# EDU_High-Speed-Design_Power_2V5_1V5.net
KiCad netlist of a schematic drawn in Altium Designer
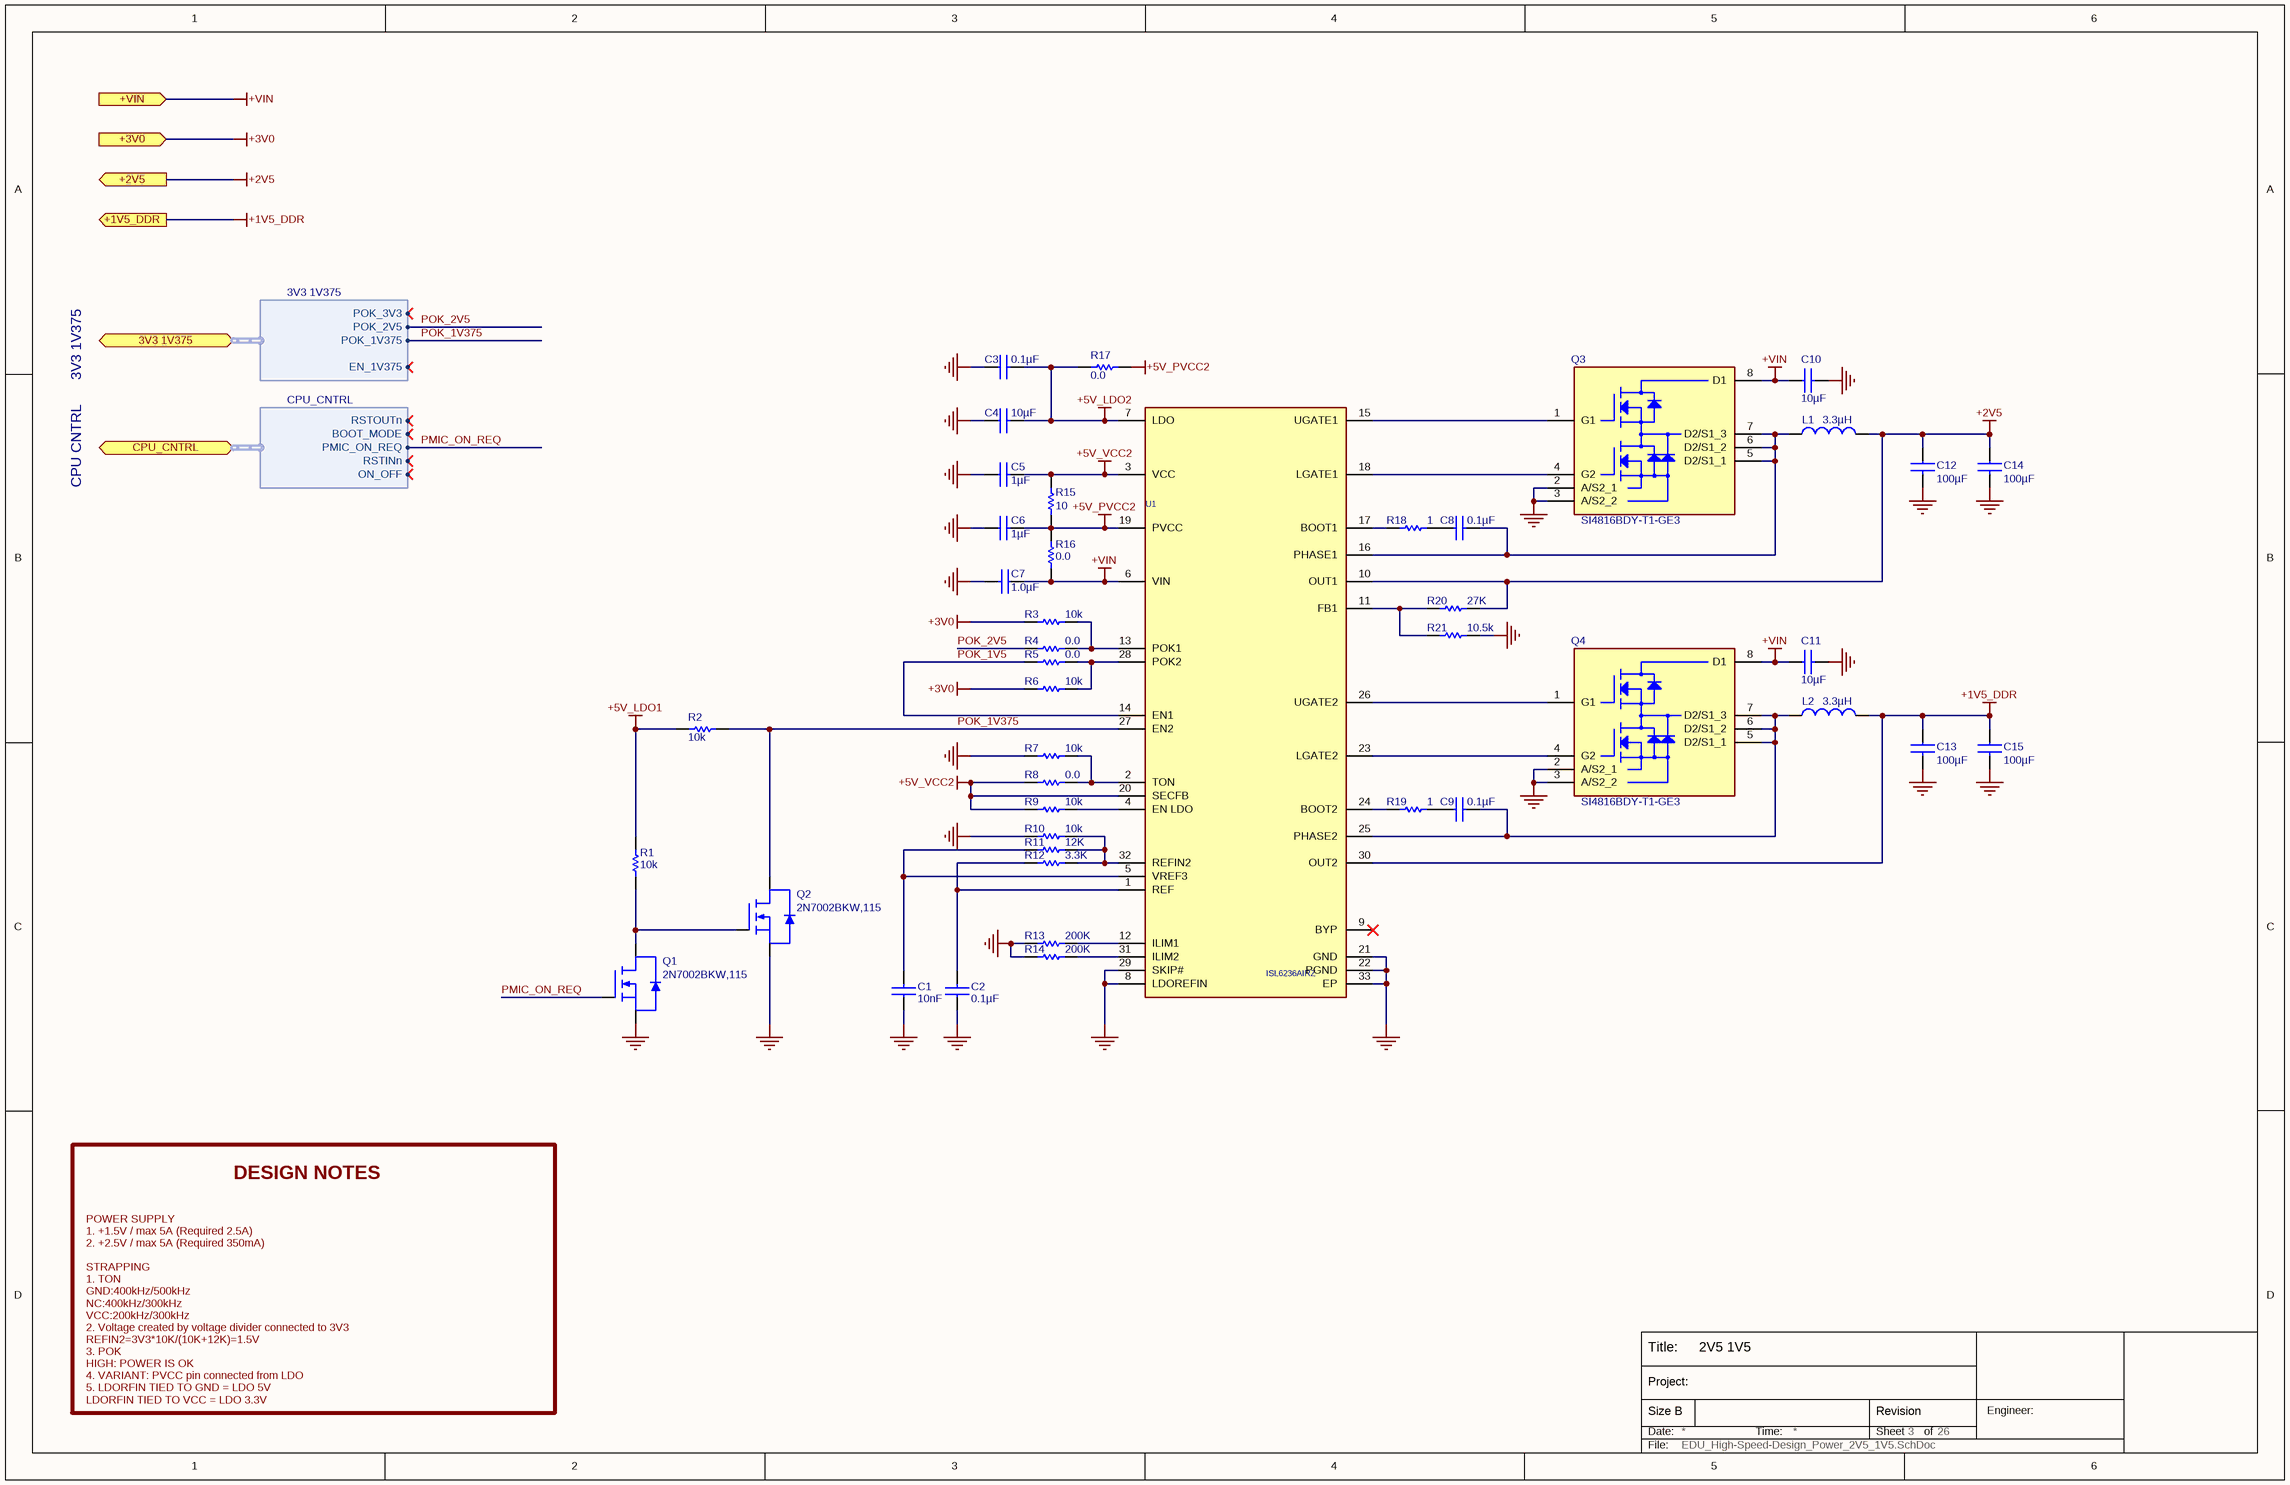
[diagram p0: EDU_High-Speed-Design_Power_2V5_1V5.SchDoc]

(export (version "E")
  (design (tool "Eeschema 10.0.6"))
  (components
    (comp (ref "C1")
      (value "10nF")
      (footprint "C0402")
      (description "CAP CER 10000PF 16V X7R 10% 0402")
      (fields
        (field (name "MANUFACTURER") "TDK Corporation")
        (field (name "MANUFACTURER PART NUMBER") "C1005X7R1C103K")
      )
      (libsource (lib "EDU_High-Speed-Design") (part "C1005X7R1C103K"))
    )
    (comp (ref "C2")
      (value "0.1µF")
      (footprint "C0402")
      (description "CAP CER .10UF 50V X5R 10% 0402")
      (fields (field (name "VOLTAGE") "50V"))
      (libsource (lib "EDU_High-Speed-Design") (part "C1005X5R1H104K"))
    )
    (comp (ref "C3")
      (value "0.1µF")
      (footprint "C0402")
      (description "CAP CER .10UF 50V X5R 10% 0402")
      (fields (field (name "VOLTAGE") "50V"))
      (libsource (lib "EDU_High-Speed-Design") (part "C1005X5R1H104K"))
    )
    (comp (ref "C4")
      (value "10µF")
      (footprint "C0603")
      (description "CAP CER 10UF 6.3V X5R 20% 0603")
      (fields (field (name "VOLTAGE") "6.3V"))
      (libsource (lib "EDU_High-Speed-Design") (part "C1608X5R0J106M"))
    )
    (comp (ref "C5")
      (value "1µF")
      (footprint "C0402")
      (description "CAP CER 1.0UF 16V X5R 0402")
      (fields (field (name "VOLTAGE") "16V"))
      (libsource (lib "EDU_High-Speed-Design") (part "C1005X5R1C105K"))
    )
    (comp (ref "C6")
      (value "1µF")
      (footprint "C0402")
      (description "CAP CER 1.0UF 16V X5R 0402")
      (fields (field (name "VOLTAGE") "16V"))
      (libsource (lib "EDU_High-Speed-Design") (part "C1005X5R1C105K"))
    )
    (comp (ref "C7")
      (value "1.0µF")
      (footprint "C0805")
      (description "CAP CER 1UF 50V X7R 0805")
      (fields (field (name "VOLTAGE") "50V"))
      (libsource (lib "EDU_High-Speed-Design") (part "GRM21BR71H105KA12L"))
    )
    (comp (ref "C8")
      (value "0.1µF")
      (footprint "C0402")
      (description "CAP CER .10UF 50V X5R 10% 0402")
      (fields (field (name "VOLTAGE") "50V"))
      (libsource (lib "EDU_High-Speed-Design") (part "C1005X5R1H104K"))
    )
    (comp (ref "C9")
      (value "0.1µF")
      (footprint "C0402")
      (description "CAP CER .10UF 50V X5R 10% 0402")
      (fields (field (name "VOLTAGE") "50V"))
      (libsource (lib "EDU_High-Speed-Design") (part "C1005X5R1H104K"))
    )
    (comp (ref "C10")
      (value "10µF")
      (footprint "C1206")
      (description "CAP CER 10UF 35V X5R 1206")
      (fields (field (name "VOLTAGE") "35V"))
      (libsource (lib "EDU_High-Speed-Design") (part "GRM31CR6YA106KA12L"))
    )
    (comp (ref "C11")
      (value "10µF")
      (footprint "C1206")
      (description "CAP CER 10UF 35V X5R 1206")
      (fields (field (name "VOLTAGE") "35V"))
      (libsource (lib "EDU_High-Speed-Design") (part "GRM31CR6YA106KA12L"))
    )
    (comp (ref "C12")
      (value "100µF")
      (footprint "C1206")
      (description "CAP CER 100UF 10V X5R 20% 1206")
      (fields (field (name "VOLTAGE") "10V"))
      (libsource (lib "EDU_High-Speed-Design") (part "C3216X5R1A107M"))
    )
    (comp (ref "C13")
      (value "100µF")
      (footprint "C1206")
      (description "CAP CER 100UF 10V X5R 20% 1206")
      (fields (field (name "VOLTAGE") "10V"))
      (libsource (lib "EDU_High-Speed-Design") (part "C3216X5R1A107M"))
    )
    (comp (ref "C14")
      (value "100µF")
      (footprint "C1206")
      (description "CAP CER 100UF 10V X5R 20% 1206")
      (fields (field (name "VOLTAGE") "10V"))
      (libsource (lib "EDU_High-Speed-Design") (part "C3216X5R1A107M"))
    )
    (comp (ref "C15")
      (value "100µF")
      (footprint "C1206")
      (description "CAP CER 100UF 10V X5R 20% 1206")
      (fields (field (name "VOLTAGE") "10V"))
      (libsource (lib "EDU_High-Speed-Design") (part "C3216X5R1A107M"))
    )
    (comp (ref "L1")
      (value "3.3µH")
      (footprint "IHLP2525")
      (description "INDUCTOR POWER 3.3UH 6A SMD")
      (libsource (lib "EDU_High-Speed-Design") (part "IHLP2525CZER3R3M01"))
    )
    (comp (ref "L2")
      (value "3.3µH")
      (footprint "IHLP2525")
      (description "INDUCTOR POWER 3.3UH 6A SMD")
      (libsource (lib "EDU_High-Speed-Design") (part "IHLP2525CZER3R3M01"))
    )
    (comp (ref "Q1")
      (value "2N7002BKW,115")
      (footprint "SOT-23-3")
      (description "MOSFET N-CH 60V 310MA SOT323")
      (libsource (lib "EDU_High-Speed-Design") (part "2N7002BKW,115"))
    )
    (comp (ref "Q2")
      (value "2N7002BKW,115")
      (footprint "SOT-23-3")
      (description "MOSFET N-CH 60V 310MA SOT323")
      (libsource (lib "EDU_High-Speed-Design") (part "2N7002BKW,115"))
    )
    (comp (ref "Q3")
      (value "SI4816BDY-T1-GE3")
      (footprint "SO8")
      (description "MOSFET DL N-CH 30V 6.8A 8-SOIC")
      (libsource (lib "EDU_High-Speed-Design") (part "SI4816BDY-T1-GE3"))
    )
    (comp (ref "Q4")
      (value "SI4816BDY-T1-GE3")
      (footprint "SO8")
      (description "MOSFET DL N-CH 30V 6.8A 8-SOIC")
      (libsource (lib "EDU_High-Speed-Design") (part "SI4816BDY-T1-GE3"))
    )
    (comp (ref "R1")
      (value "10k")
      (footprint "R0402")
      (description "RES 10.0K OHM 1/16W 1% 0402 SMD")
      (libsource (lib "EDU_High-Speed-Design") (part "RC0402FR-0710KL"))
    )
    (comp (ref "R2")
      (value "10k")
      (footprint "R0402")
      (description "RES 10.0K OHM 1/16W 1% 0402 SMD")
      (libsource (lib "EDU_High-Speed-Design") (part "RC0402FR-0710KL"))
    )
    (comp (ref "R3")
      (value "10k")
      (footprint "R0402")
      (description "RES 10.0K OHM 1/16W 1% 0402 SMD")
      (libsource (lib "EDU_High-Speed-Design") (part "RC0402FR-0710KL"))
    )
    (comp (ref "R4")
      (value "0.0")
      (footprint "R0402")
      (description "RES 0.0 OHM 1/16W 0402 SMD")
      (libsource (lib "EDU_High-Speed-Design") (part "RC0402JR-070RL"))
    )
    (comp (ref "R5")
      (value "0.0")
      (footprint "R0402")
      (description "RES 0.0 OHM 1/16W 0402 SMD")
      (libsource (lib "EDU_High-Speed-Design") (part "RC0402JR-070RL"))
    )
    (comp (ref "R6")
      (value "10k")
      (footprint "R0402")
      (description "RES 10.0K OHM 1/16W 1% 0402 SMD")
      (libsource (lib "EDU_High-Speed-Design") (part "RC0402FR-0710KL"))
    )
    (comp (ref "R7")
      (value "10k")
      (footprint "R0402")
      (description "RES 10.0K OHM 1/16W 1% 0402 SMD")
      (libsource (lib "EDU_High-Speed-Design") (part "RC0402FR-0710KL"))
    )
    (comp (ref "R8")
      (value "0.0")
      (footprint "R0402")
      (description "RES 0.0 OHM 1/16W 0402 SMD")
      (libsource (lib "EDU_High-Speed-Design") (part "RC0402JR-070RL"))
    )
    (comp (ref "R9")
      (value "10k")
      (footprint "R0402")
      (description "RES 10.0K OHM 1/16W 1% 0402 SMD")
      (libsource (lib "EDU_High-Speed-Design") (part "RC0402FR-0710KL"))
    )
    (comp (ref "R10")
      (value "10k")
      (footprint "R0402")
      (description "RES 10.0K OHM 1/16W 1% 0402 SMD")
      (libsource (lib "EDU_High-Speed-Design") (part "RC0402FR-0710KL"))
    )
    (comp (ref "R11")
      (value "12K")
      (footprint "R0402")
      (description "RES 12.0K OHM 1/16W 1% 0402 SMD")
      (libsource (lib "EDU_High-Speed-Design") (part "RC0402FR-0712KL"))
    )
    (comp (ref "R12")
      (value "3.3K")
      (footprint "R0402")
      (description "RES 3.30K OHM 1/16W 1% 0402 SMD")
      (libsource (lib "EDU_High-Speed-Design") (part "RC0402FR-073K3L"))
    )
    (comp (ref "R13")
      (value "200K")
      (footprint "R0402")
      (description "RES 200K OHM 1/16W 1% 0402 SMD")
      (libsource (lib "EDU_High-Speed-Design") (part "RC0402FR-07200KL"))
    )
    (comp (ref "R14")
      (value "200K")
      (footprint "R0402")
      (description "RES 200K OHM 1/16W 1% 0402 SMD")
      (libsource (lib "EDU_High-Speed-Design") (part "RC0402FR-07200KL"))
    )
    (comp (ref "R15")
      (value "10")
      (footprint "R0402")
      (description "RES 10.0 OHM 1/16W 1% 0402 SMD")
      (libsource (lib "EDU_High-Speed-Design") (part "RC0402FR-0710RL"))
    )
    (comp (ref "R16")
      (value "0.0")
      (footprint "R0402")
      (description "RES 0.0 OHM 1/16W 0402 SMD")
      (libsource (lib "EDU_High-Speed-Design") (part "RC0402JR-070RL"))
    )
    (comp (ref "R17")
      (value "0.0")
      (footprint "R0402")
      (description "RES 0.0 OHM 1/16W 0402 SMD")
      (libsource (lib "EDU_High-Speed-Design") (part "RC0402JR-070RL"))
    )
    (comp (ref "R18")
      (value "1")
      (footprint "R0402")
      (description "RES 1.00 OHM 1/16W 1% 0402 SM")
      (libsource (lib "EDU_High-Speed-Design") (part "RC0402FR-071RL"))
    )
    (comp (ref "R19")
      (value "1")
      (footprint "R0402")
      (description "RES 1.00 OHM 1/16W 1% 0402 SM")
      (libsource (lib "EDU_High-Speed-Design") (part "RC0402FR-071RL"))
    )
    (comp (ref "R20")
      (value "27K")
      (footprint "R0402")
      (description "RES 27.0K OHM 1/16W 1% 0402 SMD")
      (libsource (lib "EDU_High-Speed-Design") (part "RC0402FR-0727KL"))
    )
    (comp (ref "R21")
      (value "10.5k")
      (footprint "R0402")
      (description "RES 10.5K OHM 1/16W 1% 0402 SMD")
      (libsource (lib "EDU_High-Speed-Design") (part "CRCW040210K5FKED"))
    )
    (comp (ref "U1")
      (value "ISL6236AIRZ")
      (footprint "ISL6236AIRZ")
      (description "IC MAIN PWR CTRLR QUAD 32-QFN")
      (libsource (lib "EDU_High-Speed-Design") (part "ISL6236AIRZ"))
    )
  )
  (nets
    (net (code "4") (name "+1V5_DDR") (class "Default")
      (node (ref "C13") (pin "1") (pinfunction "1_1") (pintype "passive"))
      (node (ref "C15") (pin "1") (pinfunction "1_1") (pintype "passive"))
      (node (ref "L2") (pin "2") (pinfunction "2_2") (pintype "passive"))
      (node (ref "U1") (pin "30") (pinfunction "OUT2_30") (pintype "passive"))
    )
    (net (code "5") (name "+2V5") (class "Default")
      (node (ref "C12") (pin "1") (pinfunction "1_1") (pintype "passive"))
      (node (ref "C14") (pin "1") (pinfunction "1_1") (pintype "passive"))
      (node (ref "L1") (pin "2") (pinfunction "2_2") (pintype "passive"))
      (node (ref "R20") (pin "1") (pinfunction "1_1") (pintype "passive"))
      (node (ref "U1") (pin "10") (pinfunction "OUT1_10") (pintype "passive"))
    )
    (net (code "6") (name "+3V0") (class "Default")
      (node (ref "R3") (pin "2") (pinfunction "2_2") (pintype "passive"))
      (node (ref "R6") (pin "2") (pinfunction "2_2") (pintype "passive"))
    )
    (net (code "7") (name "+5V_LDO1") (class "Default")
      (node (ref "R1") (pin "2") (pinfunction "2_2") (pintype "passive"))
      (node (ref "R2") (pin "2") (pinfunction "2_2") (pintype "passive"))
    )
    (net (code "8") (name "+5V_LDO2") (class "Default")
      (node (ref "C3") (pin "2") (pinfunction "2_2") (pintype "passive"))
      (node (ref "C4") (pin "2") (pinfunction "2_2") (pintype "passive"))
      (node (ref "R17") (pin "1") (pinfunction "1_1") (pintype "passive"))
      (node (ref "U1") (pin "7") (pinfunction "LDO_7") (pintype "passive"))
    )
    (net (code "9") (name "+5V_PVCC2") (class "Default")
      (node (ref "C6") (pin "2") (pinfunction "2_2") (pintype "passive"))
      (node (ref "R15") (pin "2") (pinfunction "2_2") (pintype "passive"))
      (node (ref "R16") (pin "1") (pinfunction "1_1") (pintype "passive"))
      (node (ref "R17") (pin "2") (pinfunction "2_2") (pintype "passive"))
      (node (ref "U1") (pin "19") (pinfunction "PVCC_19") (pintype "passive"))
    )
    (net (code "10") (name "+5V_VCC2") (class "Default")
      (node (ref "C5") (pin "2") (pinfunction "2_2") (pintype "passive"))
      (node (ref "R15") (pin "1") (pinfunction "1_1") (pintype "passive"))
      (node (ref "R8") (pin "2") (pinfunction "2_2") (pintype "passive"))
      (node (ref "R9") (pin "2") (pinfunction "2_2") (pintype "passive"))
      (node (ref "U1") (pin "20") (pinfunction "SECFB_20") (pintype "passive"))
      (node (ref "U1") (pin "3") (pinfunction "VCC_3") (pintype "passive"))
    )
    (net (code "11") (name "+VIN") (class "Default")
      (node (ref "C10") (pin "1") (pinfunction "1_1") (pintype "passive"))
      (node (ref "C11") (pin "1") (pinfunction "1_1") (pintype "passive"))
      (node (ref "C7") (pin "1") (pinfunction "1_1") (pintype "passive"))
      (node (ref "Q3") (pin "8") (pinfunction "D1_8") (pintype "passive"))
      (node (ref "Q4") (pin "8") (pinfunction "D1_8") (pintype "passive"))
      (node (ref "R16") (pin "2") (pinfunction "2_2") (pintype "passive"))
      (node (ref "U1") (pin "6") (pinfunction "VIN_6") (pintype "passive"))
    )
    (net (code "12") (name "/PMIC_ON_REQ") (class "Default")
      (node (ref "Q1") (pin "1") (pinfunction "G_1") (pintype "passive"))
    )
    (net (code "13") (name "/POK_1V5") (class "Default")
      (node (ref "R5") (pin "2") (pinfunction "2_2") (pintype "passive"))
      (node (ref "U1") (pin "14") (pinfunction "EN1_14") (pintype "passive"))
    )
    (net (code "14") (name "/POK_1V375") (class "Default")
      (node (ref "Q2") (pin "3") (pinfunction "D_3") (pintype "passive"))
      (node (ref "R2") (pin "1") (pinfunction "1_1") (pintype "passive"))
      (node (ref "U1") (pin "27") (pinfunction "EN2_27") (pintype "passive"))
    )
    (net (code "15") (name "/POK_2V5") (class "Default")
      (node (ref "R4") (pin "2") (pinfunction "2_2") (pintype "passive"))
    )
    (net (code "18") (name "GND") (class "Default")
      (node (ref "C1") (pin "1") (pinfunction "1_1") (pintype "passive"))
      (node (ref "C10") (pin "2") (pinfunction "2_2") (pintype "passive"))
      (node (ref "C11") (pin "2") (pinfunction "2_2") (pintype "passive"))
      (node (ref "C12") (pin "2") (pinfunction "2_2") (pintype "passive"))
      (node (ref "C13") (pin "2") (pinfunction "2_2") (pintype "passive"))
      (node (ref "C14") (pin "2") (pinfunction "2_2") (pintype "passive"))
      (node (ref "C15") (pin "2") (pinfunction "2_2") (pintype "passive"))
      (node (ref "C2") (pin "1") (pinfunction "1_1") (pintype "passive"))
      (node (ref "C3") (pin "1") (pinfunction "1_1") (pintype "passive"))
      (node (ref "C4") (pin "1") (pinfunction "1_1") (pintype "passive"))
      (node (ref "C5") (pin "1") (pinfunction "1_1") (pintype "passive"))
      (node (ref "C6") (pin "1") (pinfunction "1_1") (pintype "passive"))
      (node (ref "C7") (pin "2") (pinfunction "2_2") (pintype "passive"))
      (node (ref "Q1") (pin "2") (pinfunction "S_2") (pintype "passive"))
      (node (ref "Q2") (pin "2") (pinfunction "S_2") (pintype "passive"))
      (node (ref "Q3") (pin "2") (pinfunction "A/S2_1_2") (pintype "passive"))
      (node (ref "Q3") (pin "3") (pinfunction "A/S2_2_3") (pintype "passive"))
      (node (ref "Q4") (pin "2") (pinfunction "A/S2_1_2") (pintype "passive"))
      (node (ref "Q4") (pin "3") (pinfunction "A/S2_2_3") (pintype "passive"))
      (node (ref "R10") (pin "2") (pinfunction "2_2") (pintype "passive"))
      (node (ref "R13") (pin "2") (pinfunction "2_2") (pintype "passive"))
      (node (ref "R14") (pin "2") (pinfunction "2_2") (pintype "passive"))
      (node (ref "R21") (pin "1") (pinfunction "1_1") (pintype "passive"))
      (node (ref "R7") (pin "2") (pinfunction "2_2") (pintype "passive"))
      (node (ref "U1") (pin "21") (pinfunction "GND_21") (pintype "passive"))
      (node (ref "U1") (pin "22") (pinfunction "PGND_22") (pintype "passive"))
      (node (ref "U1") (pin "29") (pinfunction "SKIP#_29") (pintype "passive"))
      (node (ref "U1") (pin "33") (pinfunction "EP_33") (pintype "passive"))
      (node (ref "U1") (pin "8") (pinfunction "LDOREFIN_8") (pintype "passive"))
    )
    (net (code "19") (name "Net-(C8-Pad1)") (class "Default")
      (node (ref "C8") (pin "1") (pinfunction "1_1") (pintype "passive"))
      (node (ref "R18") (pin "1") (pinfunction "1_1") (pintype "passive"))
    )
    (net (code "20") (name "Net-(C9-Pad1)") (class "Default")
      (node (ref "C9") (pin "1") (pinfunction "1_1") (pintype "passive"))
      (node (ref "R19") (pin "1") (pinfunction "1_1") (pintype "passive"))
    )
    (net (code "21") (name "Net-(Q1-D)") (class "Default")
      (node (ref "Q1") (pin "3") (pinfunction "D_3") (pintype "passive"))
      (node (ref "Q2") (pin "1") (pinfunction "G_1") (pintype "passive"))
      (node (ref "R1") (pin "1") (pinfunction "1_1") (pintype "passive"))
    )
    (net (code "22") (name "Net-(Q3-D2{slash}S1_1)") (class "Default")
      (node (ref "C8") (pin "2") (pinfunction "2_2") (pintype "passive"))
      (node (ref "L1") (pin "1") (pinfunction "1_1") (pintype "passive"))
      (node (ref "Q3") (pin "5") (pinfunction "D2/S1_1_5") (pintype "passive"))
      (node (ref "Q3") (pin "6") (pinfunction "D2/S1_2_6") (pintype "passive"))
      (node (ref "Q3") (pin "7") (pinfunction "D2/S1_3_7") (pintype "passive"))
      (node (ref "U1") (pin "16") (pinfunction "PHASE1_16") (pintype "passive"))
    )
    (net (code "23") (name "Net-(Q3-G1)") (class "Default")
      (node (ref "Q3") (pin "1") (pinfunction "G1_1") (pintype "passive"))
      (node (ref "U1") (pin "15") (pinfunction "UGATE1_15") (pintype "passive"))
    )
    (net (code "24") (name "Net-(Q3-G2)") (class "Default")
      (node (ref "Q3") (pin "4") (pinfunction "G2_4") (pintype "passive"))
      (node (ref "U1") (pin "18") (pinfunction "LGATE1_18") (pintype "passive"))
    )
    (net (code "25") (name "Net-(Q4-D2{slash}S1_1)") (class "Default")
      (node (ref "C9") (pin "2") (pinfunction "2_2") (pintype "passive"))
      (node (ref "L2") (pin "1") (pinfunction "1_1") (pintype "passive"))
      (node (ref "Q4") (pin "5") (pinfunction "D2/S1_1_5") (pintype "passive"))
      (node (ref "Q4") (pin "6") (pinfunction "D2/S1_2_6") (pintype "passive"))
      (node (ref "Q4") (pin "7") (pinfunction "D2/S1_3_7") (pintype "passive"))
      (node (ref "U1") (pin "25") (pinfunction "PHASE2_25") (pintype "passive"))
    )
    (net (code "26") (name "Net-(Q4-G1)") (class "Default")
      (node (ref "Q4") (pin "1") (pinfunction "G1_1") (pintype "passive"))
      (node (ref "U1") (pin "26") (pinfunction "UGATE2_26") (pintype "passive"))
    )
    (net (code "27") (name "Net-(Q4-G2)") (class "Default")
      (node (ref "Q4") (pin "4") (pinfunction "G2_4") (pintype "passive"))
      (node (ref "U1") (pin "23") (pinfunction "LGATE2_23") (pintype "passive"))
    )
    (net (code "28") (name "Net-(U1-BOOT1)") (class "Default")
      (node (ref "R18") (pin "2") (pinfunction "2_2") (pintype "passive"))
      (node (ref "U1") (pin "17") (pinfunction "BOOT1_17") (pintype "passive"))
    )
    (net (code "29") (name "Net-(U1-BOOT2)") (class "Default")
      (node (ref "R19") (pin "2") (pinfunction "2_2") (pintype "passive"))
      (node (ref "U1") (pin "24") (pinfunction "BOOT2_24") (pintype "passive"))
    )
    (net (code "30") (name "Net-(U1-EN_LDO)") (class "Default")
      (node (ref "R9") (pin "1") (pinfunction "1_1") (pintype "passive"))
      (node (ref "U1") (pin "4") (pinfunction "EN_LDO_4") (pintype "passive"))
    )
    (net (code "31") (name "Net-(U1-FB1)") (class "Default")
      (node (ref "R20") (pin "2") (pinfunction "2_2") (pintype "passive"))
      (node (ref "R21") (pin "2") (pinfunction "2_2") (pintype "passive"))
      (node (ref "U1") (pin "11") (pinfunction "FB1_11") (pintype "passive"))
    )
    (net (code "32") (name "Net-(U1-ILIM1)") (class "Default")
      (node (ref "R13") (pin "1") (pinfunction "1_1") (pintype "passive"))
      (node (ref "U1") (pin "12") (pinfunction "ILIM1_12") (pintype "passive"))
    )
    (net (code "33") (name "Net-(U1-ILIM2)") (class "Default")
      (node (ref "R14") (pin "1") (pinfunction "1_1") (pintype "passive"))
      (node (ref "U1") (pin "31") (pinfunction "ILIM2_31") (pintype "passive"))
    )
    (net (code "34") (name "Net-(U1-POK1)") (class "Default")
      (node (ref "R3") (pin "1") (pinfunction "1_1") (pintype "passive"))
      (node (ref "R4") (pin "1") (pinfunction "1_1") (pintype "passive"))
      (node (ref "U1") (pin "13") (pinfunction "POK1_13") (pintype "passive"))
    )
    (net (code "35") (name "Net-(U1-POK2)") (class "Default")
      (node (ref "R5") (pin "1") (pinfunction "1_1") (pintype "passive"))
      (node (ref "R6") (pin "1") (pinfunction "1_1") (pintype "passive"))
      (node (ref "U1") (pin "28") (pinfunction "POK2_28") (pintype "passive"))
    )
    (net (code "36") (name "Net-(U1-REF)") (class "Default")
      (node (ref "C2") (pin "2") (pinfunction "2_2") (pintype "passive"))
      (node (ref "R12") (pin "2") (pinfunction "2_2") (pintype "passive"))
      (node (ref "U1") (pin "1") (pinfunction "REF_1") (pintype "passive"))
    )
    (net (code "37") (name "Net-(U1-REFIN2)") (class "Default")
      (node (ref "R10") (pin "1") (pinfunction "1_1") (pintype "passive"))
      (node (ref "R11") (pin "1") (pinfunction "1_1") (pintype "passive"))
      (node (ref "R12") (pin "1") (pinfunction "1_1") (pintype "passive"))
      (node (ref "U1") (pin "32") (pinfunction "REFIN2_32") (pintype "passive"))
    )
    (net (code "38") (name "Net-(U1-TON)") (class "Default")
      (node (ref "R7") (pin "1") (pinfunction "1_1") (pintype "passive"))
      (node (ref "R8") (pin "1") (pinfunction "1_1") (pintype "passive"))
      (node (ref "U1") (pin "2") (pinfunction "TON_2") (pintype "passive"))
    )
    (net (code "39") (name "Net-(U1-VREF3)") (class "Default")
      (node (ref "C1") (pin "2") (pinfunction "2_2") (pintype "passive"))
      (node (ref "R11") (pin "2") (pinfunction "2_2") (pintype "passive"))
      (node (ref "U1") (pin "5") (pinfunction "VREF3_5") (pintype "passive"))
    )
    (net (code "40") (name "unconnected-(U1-BYP-Pad9)") (class "Default")
      (node (ref "U1") (pin "9") (pinfunction "BYP_9") (pintype "passive+no_connect"))
    )
  )
)
